# Preamp.net
KiCad netlist of a schematic drawn in Altium Designer
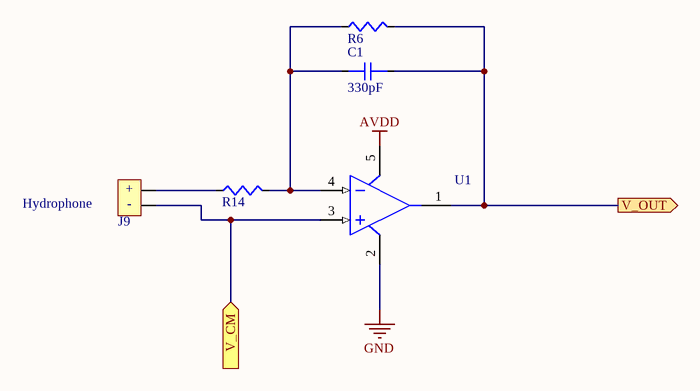
[diagram p0: Preamp.SchDoc]

(export (version "E")
  (design (tool "Eeschema 10.0.6"))
  (components
    (comp (ref "C1")
      (value "330pF")
      (footprint "C0603")
      (description "CAP CER 330PF 50V X7R 0603")
      (fields (field (name "TOLERANCE") "10%"))
      (libsource (lib "DAQ") (part "CC0603KRX7R9BB331"))
    )
    (comp (ref "J9")
      (value "J")
      (footprint "hydrophones_sma_conn")
      (libsource (lib "DAQ") (part "hydrophone_connector"))
    )
    (comp (ref "R6")
      (value "1M")
      (footprint "R0603")
      (description "RES SMD 1M OHM 1% 1/8W 0603")
      (fields (field (name "TOLERANCE") "1%"))
      (libsource (lib "DAQ") (part "MCT06030C1004FP500"))
    )
    (comp (ref "R14")
      (value "330")
      (footprint "R0603")
      (description "RES SMD 330 OHM 1% 1/8W 0603")
      (fields (field (name "TOLERANCE") "1%"))
      (libsource (lib "DAQ") (part "MCT06030C3300FP500"))
    )
    (comp (ref "U1") (value "OPA325") (footprint "SOT-23-5") (libsource (lib "DAQ") (part "OPA325IDBVR")))
  )
  (nets
    (net (code "1") (name "/V_CM") (class "Default")
      (node (ref "J9") (pin "2") (pinfunction "2_2") (pintype "passive"))
      (node (ref "U1") (pin "3") (pinfunction "+IN_3") (pintype "input"))
    )
    (net (code "2") (name "/V_OUT") (class "Default")
      (node (ref "C1") (pin "2") (pinfunction "2_2") (pintype "passive"))
      (node (ref "R6") (pin "2") (pinfunction "2_2") (pintype "passive"))
      (node (ref "U1") (pin "1") (pinfunction "OUT_1") (pintype "passive"))
    )
    (net (code "3") (name "AVDD") (class "Default")
      (node (ref "U1") (pin "5") (pinfunction "VS+_5") (pintype "power_in"))
    )
    (net (code "4") (name "GND") (class "Default")
      (node (ref "U1") (pin "2") (pinfunction "VS-_2") (pintype "power_in"))
    )
    (net (code "5") (name "Net-(J9-Pad1)") (class "Default")
      (node (ref "J9") (pin "1") (pinfunction "1_1") (pintype "passive"))
      (node (ref "R14") (pin "1") (pinfunction "1_1") (pintype "passive"))
    )
    (net (code "6") (name "Net-(U1--IN)") (class "Default")
      (node (ref "C1") (pin "1") (pinfunction "1_1") (pintype "passive"))
      (node (ref "R14") (pin "2") (pinfunction "2_2") (pintype "passive"))
      (node (ref "R6") (pin "1") (pinfunction "1_1") (pintype "passive"))
      (node (ref "U1") (pin "4") (pinfunction "-IN_4") (pintype "input"))
    )
  )
)
